# MB_RF.net
KiCad netlist of a schematic drawn in Altium Designer
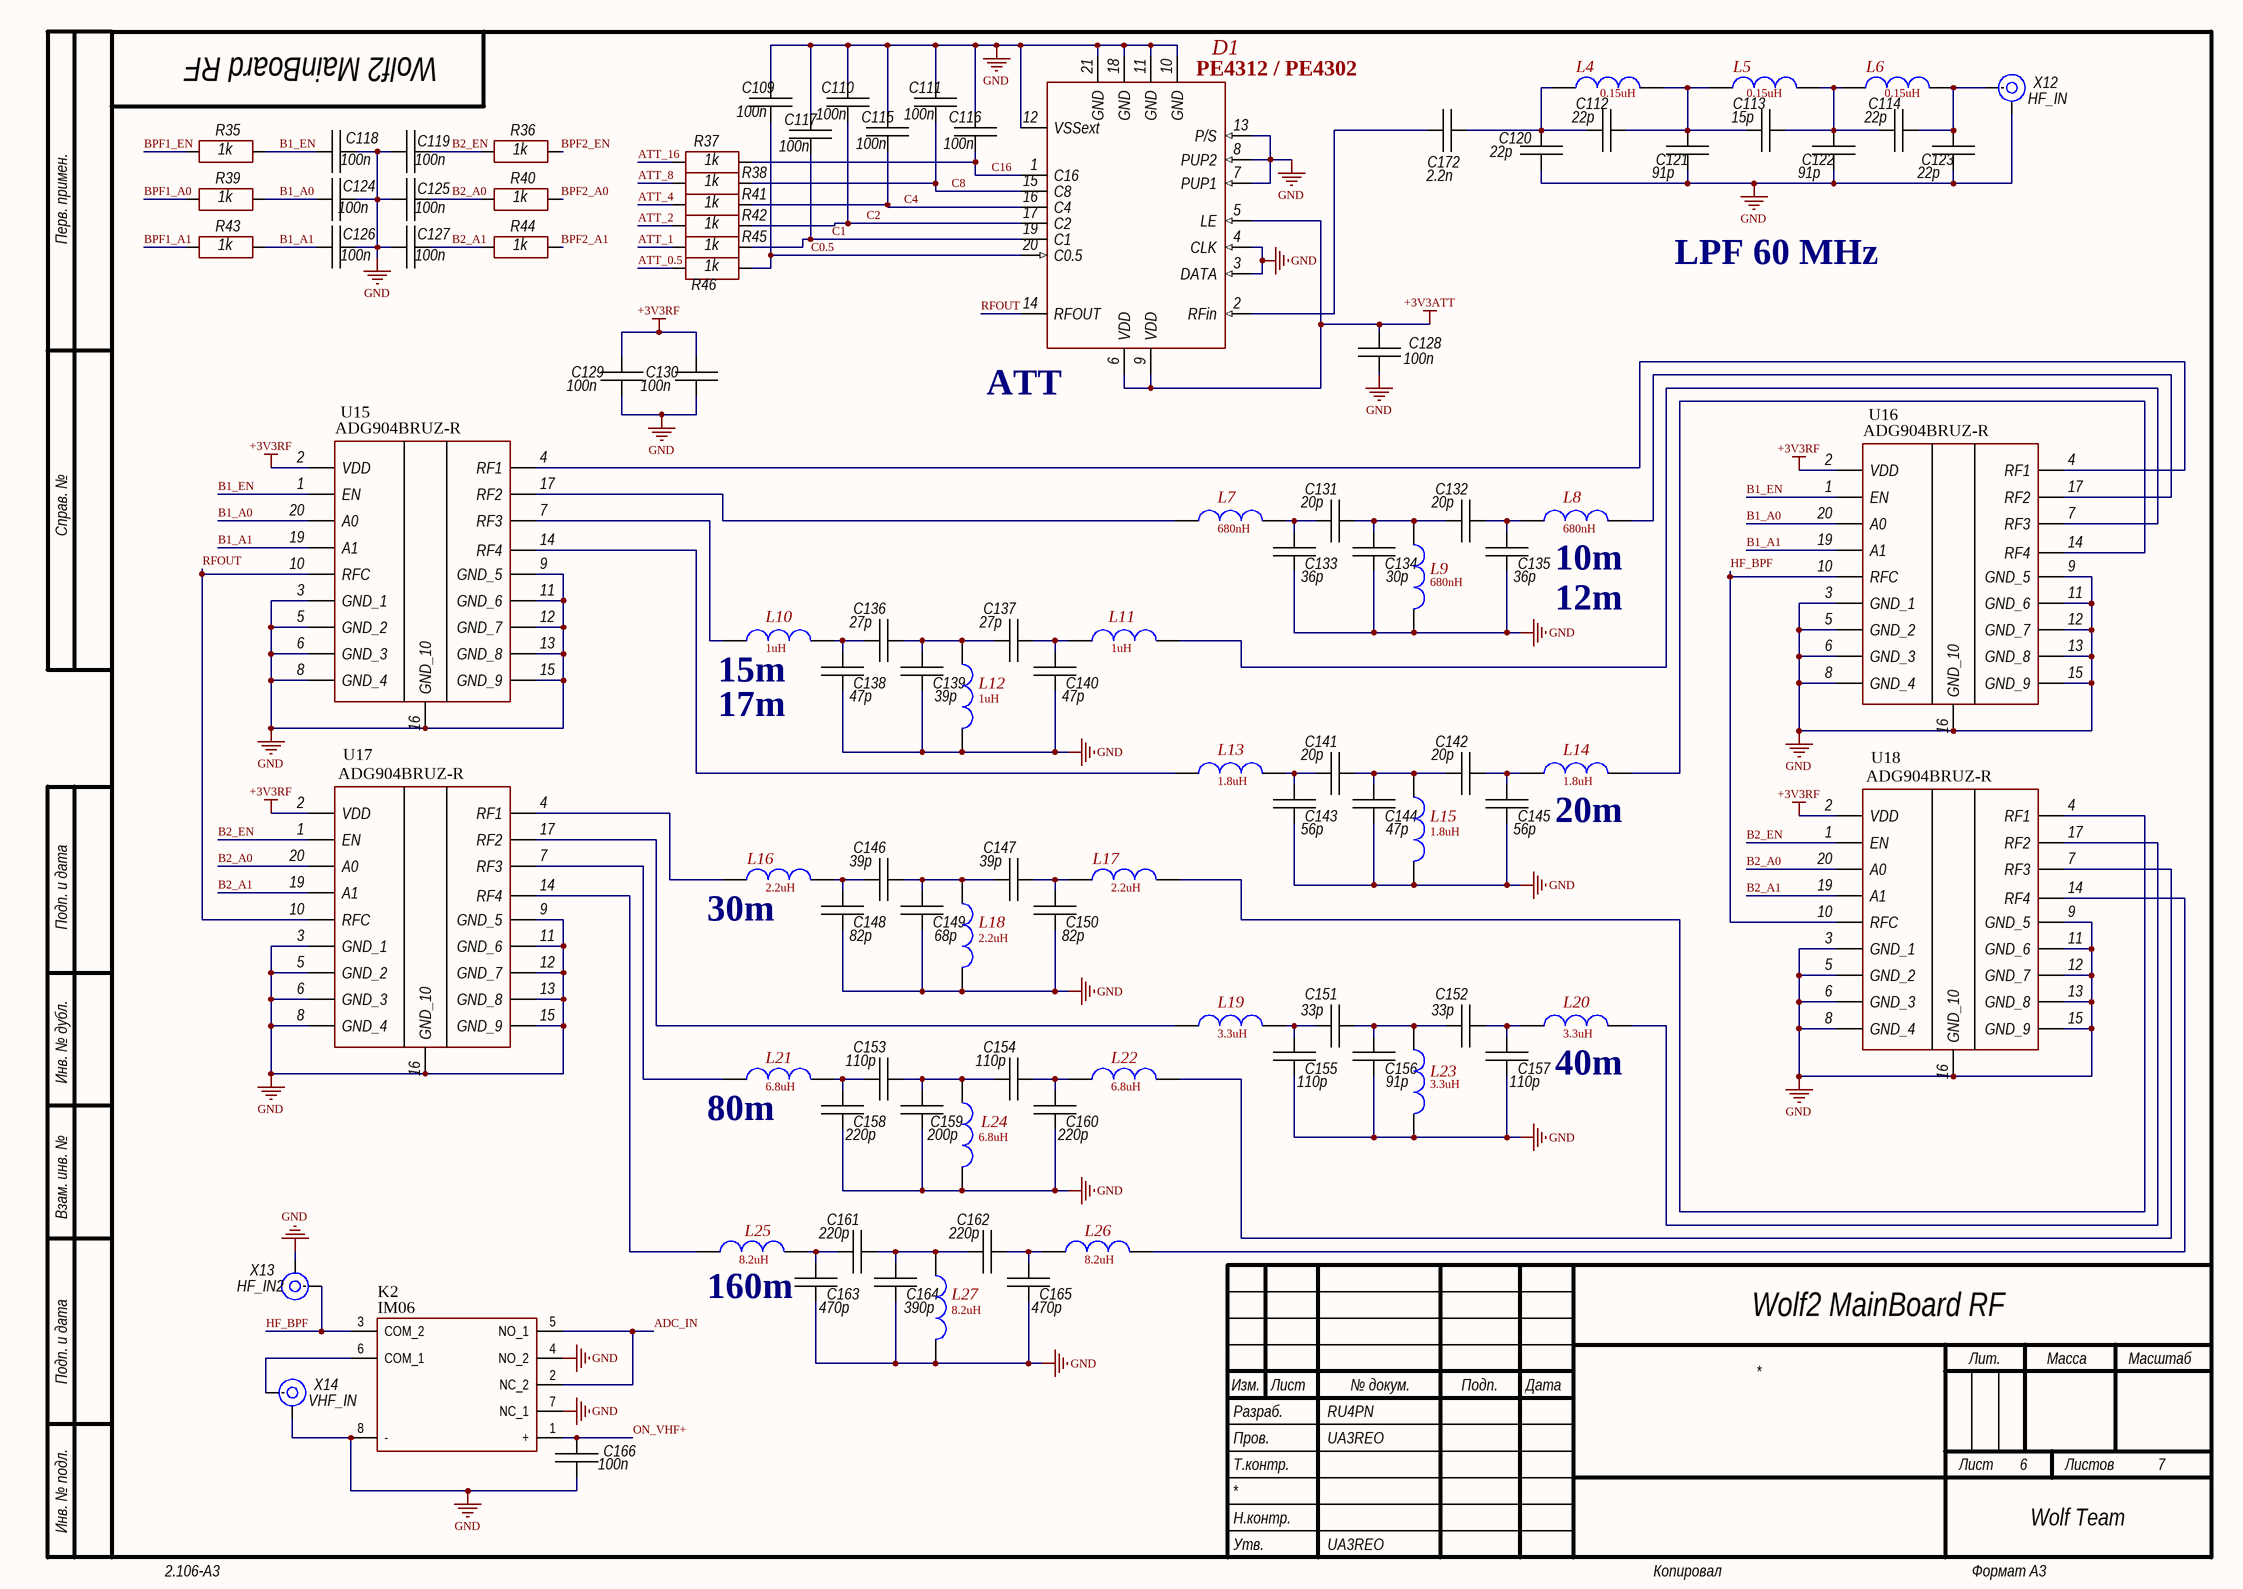
[diagram p0: MB_RF.SchDoc]

(export (version "E")
  (design (tool "Eeschema 10.0.6"))
  (components
    (comp (ref "C109")
      (value "100n")
      (footprint "standard:CH0805C")
      (libsource (lib "Discrete") (part "Capacitor"))
    )
    (comp (ref "C110")
      (value "100n")
      (footprint "standard:CH0805C")
      (libsource (lib "Discrete") (part "Capacitor"))
    )
    (comp (ref "C111")
      (value "100n")
      (footprint "standard:CH0805C")
      (libsource (lib "Discrete") (part "Capacitor"))
    )
    (comp (ref "C112")
      (value "22p")
      (footprint "standard:CH0805C")
      (libsource (lib "Discrete") (part "Capacitor"))
    )
    (comp (ref "C113")
      (value "15p")
      (footprint "standard:CH0805C")
      (libsource (lib "Discrete") (part "Capacitor"))
    )
    (comp (ref "C114")
      (value "22p")
      (footprint "standard:CH0805C")
      (libsource (lib "Discrete") (part "Capacitor"))
    )
    (comp (ref "C115")
      (value "100n")
      (footprint "standard:CH0805C")
      (libsource (lib "Discrete") (part "Capacitor"))
    )
    (comp (ref "C116")
      (value "100n")
      (footprint "standard:CH0805C")
      (libsource (lib "Discrete") (part "Capacitor"))
    )
    (comp (ref "C117")
      (value "100n")
      (footprint "standard:CH0805C")
      (libsource (lib "Discrete") (part "Capacitor"))
    )
    (comp (ref "C118")
      (value "100n")
      (footprint "standard:CH0805C")
      (libsource (lib "Discrete") (part "Capacitor"))
    )
    (comp (ref "C119")
      (value "100n")
      (footprint "standard:CH0805C")
      (libsource (lib "Discrete") (part "Capacitor"))
    )
    (comp (ref "C120")
      (value "22p")
      (footprint "standard:CH0805C")
      (libsource (lib "Discrete") (part "Capacitor"))
    )
    (comp (ref "C121")
      (value "91p")
      (footprint "standard:CH0805C")
      (libsource (lib "Discrete") (part "Capacitor"))
    )
    (comp (ref "C122")
      (value "91p")
      (footprint "standard:CH0805C")
      (libsource (lib "Discrete") (part "Capacitor"))
    )
    (comp (ref "C123")
      (value "22p")
      (footprint "standard:CH0805C")
      (libsource (lib "Discrete") (part "Capacitor"))
    )
    (comp (ref "C124")
      (value "100n")
      (footprint "standard:CH0805C")
      (libsource (lib "Discrete") (part "Capacitor"))
    )
    (comp (ref "C125")
      (value "100n")
      (footprint "standard:CH0805C")
      (libsource (lib "Discrete") (part "Capacitor"))
    )
    (comp (ref "C126")
      (value "100n")
      (footprint "standard:CH0805C")
      (libsource (lib "") (part "Capacitor_2"))
    )
    (comp (ref "C127")
      (value "100n")
      (footprint "standard:CH0805C")
      (libsource (lib "") (part "Capacitor_2"))
    )
    (comp (ref "C128")
      (value "100n")
      (footprint "standard:CH0805C")
      (libsource (lib "Discrete") (part "Capacitor"))
    )
    (comp (ref "C129")
      (value "100n")
      (footprint "standard:CH0805C")
      (libsource (lib "Discrete") (part "Capacitor"))
    )
    (comp (ref "C130")
      (value "100n")
      (footprint "standard:CH0805C")
      (libsource (lib "Discrete") (part "Capacitor"))
    )
    (comp (ref "C131") (value "20p") (footprint "standard:CH0805C") (libsource (lib "") (part "Capacitor_1")))
    (comp (ref "C132")
      (value "20p")
      (footprint "standard:CH0805C")
      (libsource (lib "Discrete") (part "Capacitor"))
    )
    (comp (ref "C133")
      (value "36p")
      (footprint "standard:CH0805C")
      (libsource (lib "Discrete") (part "Capacitor"))
    )
    (comp (ref "C134")
      (value "30p")
      (footprint "standard:CH0805C")
      (libsource (lib "Discrete") (part "Capacitor"))
    )
    (comp (ref "C135")
      (value "36p")
      (footprint "standard:CH0805C")
      (libsource (lib "Discrete") (part "Capacitor"))
    )
    (comp (ref "C136")
      (value "27p")
      (footprint "standard:CH0805C")
      (libsource (lib "Discrete") (part "Capacitor"))
    )
    (comp (ref "C137")
      (value "27p")
      (footprint "standard:CH0805C")
      (libsource (lib "Discrete") (part "Capacitor"))
    )
    (comp (ref "C138")
      (value "47p")
      (footprint "standard:CH0805C")
      (libsource (lib "Discrete") (part "Capacitor"))
    )
    (comp (ref "C139")
      (value "39p")
      (footprint "standard:CH0805C")
      (libsource (lib "Discrete") (part "Capacitor"))
    )
    (comp (ref "C140")
      (value "47p")
      (footprint "standard:CH0805C")
      (libsource (lib "Discrete") (part "Capacitor"))
    )
    (comp (ref "C141") (value "20p") (footprint "standard:CH0805C") (libsource (lib "") (part "Capacitor_1")))
    (comp (ref "C142")
      (value "20p")
      (footprint "standard:CH0805C")
      (libsource (lib "Discrete") (part "Capacitor"))
    )
    (comp (ref "C143")
      (value "56p")
      (footprint "standard:CH0805C")
      (libsource (lib "Discrete") (part "Capacitor"))
    )
    (comp (ref "C144")
      (value "47p")
      (footprint "standard:CH0805C")
      (libsource (lib "Discrete") (part "Capacitor"))
    )
    (comp (ref "C145")
      (value "56p")
      (footprint "standard:CH0805C")
      (libsource (lib "Discrete") (part "Capacitor"))
    )
    (comp (ref "C146")
      (value "39p")
      (footprint "standard:CH0805C")
      (libsource (lib "Discrete") (part "Capacitor"))
    )
    (comp (ref "C147")
      (value "39p")
      (footprint "standard:CH0805C")
      (libsource (lib "Discrete") (part "Capacitor"))
    )
    (comp (ref "C148")
      (value "82p")
      (footprint "standard:CH0805C")
      (libsource (lib "Discrete") (part "Capacitor"))
    )
    (comp (ref "C149")
      (value "68p")
      (footprint "standard:CH0805C")
      (libsource (lib "Discrete") (part "Capacitor"))
    )
    (comp (ref "C150")
      (value "82p")
      (footprint "standard:CH0805C")
      (libsource (lib "Discrete") (part "Capacitor"))
    )
    (comp (ref "C151") (value "33p") (footprint "standard:CH0805C") (libsource (lib "") (part "Capacitor_1")))
    (comp (ref "C152")
      (value "33p")
      (footprint "standard:CH0805C")
      (libsource (lib "Discrete") (part "Capacitor"))
    )
    (comp (ref "C153")
      (value "110p")
      (footprint "standard:CH0805C")
      (libsource (lib "Discrete") (part "Capacitor"))
    )
    (comp (ref "C154")
      (value "110p")
      (footprint "standard:CH0805C")
      (libsource (lib "Discrete") (part "Capacitor"))
    )
    (comp (ref "C155")
      (value "110p")
      (footprint "standard:CH0805C")
      (libsource (lib "Discrete") (part "Capacitor"))
    )
    (comp (ref "C156")
      (value "91p")
      (footprint "standard:CH0805C")
      (libsource (lib "Discrete") (part "Capacitor"))
    )
    (comp (ref "C157")
      (value "110p")
      (footprint "standard:CH0805C")
      (libsource (lib "Discrete") (part "Capacitor"))
    )
    (comp (ref "C158")
      (value "220p")
      (footprint "standard:CH0805C")
      (libsource (lib "Discrete") (part "Capacitor"))
    )
    (comp (ref "C159")
      (value "200p")
      (footprint "standard:CH0805C")
      (libsource (lib "Discrete") (part "Capacitor"))
    )
    (comp (ref "C160")
      (value "220p")
      (footprint "standard:CH0805C")
      (libsource (lib "Discrete") (part "Capacitor"))
    )
    (comp (ref "C161")
      (value "220p")
      (footprint "standard:CH0805C")
      (libsource (lib "Discrete") (part "Capacitor"))
    )
    (comp (ref "C162")
      (value "220p")
      (footprint "standard:CH0805C")
      (libsource (lib "Discrete") (part "Capacitor"))
    )
    (comp (ref "C163")
      (value "470p")
      (footprint "standard:CH0805C")
      (libsource (lib "Discrete") (part "Capacitor"))
    )
    (comp (ref "C164")
      (value "390p")
      (footprint "standard:CH0805C")
      (libsource (lib "Discrete") (part "Capacitor"))
    )
    (comp (ref "C165")
      (value "470p")
      (footprint "standard:CH0805C")
      (libsource (lib "Discrete") (part "Capacitor"))
    )
    (comp (ref "C166")
      (value "100n")
      (footprint "standard:CH0805C")
      (libsource (lib "Discrete") (part "Capacitor"))
    )
    (comp (ref "C172")
      (value "2.2n")
      (footprint "standard:CH0805C")
      (libsource (lib "Discrete") (part "Capacitor"))
    )
    (comp (ref "D1")
      (value "PE4312 / PE4302")
      (footprint "20-QFN (4x4)")
      (libsource (lib "Digital") (part "PE4312-№1"))
    )
    (comp (ref "K2") (value "IM06") (footprint "IM06") (libsource (lib "Relay") (part "IM06-V1")))
    (comp (ref "L4") (value "0.15uH") (footprint "CH0805L") (libsource (lib "Discrete") (part "Inductor-2")))
    (comp (ref "L5") (value "0.15uH") (footprint "CH0805L") (libsource (lib "Discrete") (part "Inductor-2")))
    (comp (ref "L6") (value "0.15uH") (footprint "CH0805L") (libsource (lib "Discrete") (part "Inductor-2")))
    (comp (ref "L7") (value "680nH") (footprint "CH0805L") (libsource (lib "Discrete") (part "Inductor-2")))
    (comp (ref "L8") (value "680nH") (footprint "CH0805L") (libsource (lib "Discrete") (part "Inductor-2")))
    (comp (ref "L9") (value "680nH") (footprint "CH0805L") (libsource (lib "Discrete") (part "Inductor-2")))
    (comp (ref "L10") (value "1uH") (footprint "CH0805L") (libsource (lib "Discrete") (part "Inductor-2")))
    (comp (ref "L11") (value "1uH") (footprint "CH0805L") (libsource (lib "Discrete") (part "Inductor-2")))
    (comp (ref "L12") (value "1uH") (footprint "CH0805L") (libsource (lib "Discrete") (part "Inductor-2")))
    (comp (ref "L13") (value "1.8uH") (footprint "CH0805L") (libsource (lib "Discrete") (part "Inductor-2")))
    (comp (ref "L14") (value "1.8uH") (footprint "CH0805L") (libsource (lib "Discrete") (part "Inductor-2")))
    (comp (ref "L15") (value "1.8uH") (footprint "CH0805L") (libsource (lib "Discrete") (part "Inductor-2")))
    (comp (ref "L16") (value "2.2uH") (footprint "CH0805L") (libsource (lib "Discrete") (part "Inductor-2")))
    (comp (ref "L17") (value "2.2uH") (footprint "CH0805L") (libsource (lib "Discrete") (part "Inductor-2")))
    (comp (ref "L18") (value "2.2uH") (footprint "CH0805L") (libsource (lib "Discrete") (part "Inductor-2")))
    (comp (ref "L19") (value "3.3uH") (footprint "CH0805L") (libsource (lib "Discrete") (part "Inductor-2")))
    (comp (ref "L20") (value "3.3uH") (footprint "CH0805L") (libsource (lib "Discrete") (part "Inductor-2")))
    (comp (ref "L21") (value "6.8uH") (footprint "CH0805L") (libsource (lib "Discrete") (part "Inductor-2")))
    (comp (ref "L22") (value "6.8uH") (footprint "CH0805L") (libsource (lib "Discrete") (part "Inductor-2")))
    (comp (ref "L23") (value "3.3uH") (footprint "CH0805L") (libsource (lib "Discrete") (part "Inductor-2")))
    (comp (ref "L24") (value "6.8uH") (footprint "CH0805L") (libsource (lib "Discrete") (part "Inductor-2")))
    (comp (ref "L25") (value "8.2uH") (footprint "CH0805L") (libsource (lib "Discrete") (part "Inductor-2")))
    (comp (ref "L26") (value "8.2uH") (footprint "CH0805L") (libsource (lib "Discrete") (part "Inductor-2")))
    (comp (ref "L27") (value "8.2uH") (footprint "CH0805L") (libsource (lib "Discrete") (part "Inductor-2")))
    (comp (ref "R35")
      (value "1k")
      (footprint "standard:CH0805R")
      (libsource (lib "Discrete") (part "Resistor"))
    )
    (comp (ref "R36")
      (value "1k")
      (footprint "standard:CH0805R")
      (libsource (lib "Discrete") (part "Resistor"))
    )
    (comp (ref "R37")
      (value "1k")
      (footprint "standard:CH0805R")
      (libsource (lib "Discrete") (part "Resistor"))
    )
    (comp (ref "R38")
      (value "1k")
      (footprint "standard:CH0805R")
      (libsource (lib "Discrete") (part "Resistor"))
    )
    (comp (ref "R39")
      (value "1k")
      (footprint "standard:CH0805R")
      (libsource (lib "Discrete") (part "Resistor"))
    )
    (comp (ref "R40")
      (value "1k")
      (footprint "standard:CH0805R")
      (libsource (lib "Discrete") (part "Resistor"))
    )
    (comp (ref "R41")
      (value "1k")
      (footprint "standard:CH0805R")
      (libsource (lib "Discrete") (part "Resistor"))
    )
    (comp (ref "R42")
      (value "1k")
      (footprint "standard:CH0805R")
      (libsource (lib "Discrete") (part "Resistor"))
    )
    (comp (ref "R43") (value "1k") (footprint "standard:CH0805R") (libsource (lib "") (part "Resistor_1")))
    (comp (ref "R44") (value "1k") (footprint "standard:CH0805R") (libsource (lib "") (part "Resistor_1")))
    (comp (ref "R45") (value "1k") (footprint "standard:CH0805R") (libsource (lib "") (part "Resistor_1")))
    (comp (ref "R46")
      (value "1k")
      (footprint "standard:CH0805R")
      (libsource (lib "Discrete") (part "Resistor"))
    )
    (comp (ref "U15")
      (value "ADG904BRUZ-R")
      (footprint "20-TSSOP")
      (libsource (lib "Digital") (part "ADG904BRUZ-R"))
    )
    (comp (ref "U16")
      (value "ADG904BRUZ-R")
      (footprint "20-TSSOP")
      (libsource (lib "Digital") (part "ADG904BRUZ-R"))
    )
    (comp (ref "U17")
      (value "ADG904BRUZ-R")
      (footprint "20-TSSOP")
      (libsource (lib "Digital") (part "ADG904BRUZ-R"))
    )
    (comp (ref "U18")
      (value "ADG904BRUZ-R")
      (footprint "20-TSSOP")
      (libsource (lib "Digital") (part "ADG904BRUZ-R"))
    )
    (comp (ref "X12")
      (value "HF_IN")
      (footprint "custom:CON: SMA")
      (description "RF")
      (libsource (lib "Connectors") (part "SMA"))
    )
    (comp (ref "X13")
      (value "HF_IN2")
      (footprint "custom:CON: SMA")
      (description "RF")
      (libsource (lib "Connectors") (part "SMA"))
    )
    (comp (ref "X14")
      (value "VHF_IN")
      (footprint "custom:CON: SMA")
      (description "RF")
      (libsource (lib "Connectors") (part "SMA"))
    )
  )
  (nets
    (net (code "1") (name "+3V3ATT") (class "Default")
      (node (ref "C128") (pin "1") (pinfunction "1_1") (pintype "power_in"))
      (node (ref "D1") (pin "5") (pinfunction "LE_5") (pintype "input"))
      (node (ref "D1") (pin "6") (pinfunction "VDD_6") (pintype "passive"))
      (node (ref "D1") (pin "9") (pinfunction "VDD_9") (pintype "passive"))
    )
    (net (code "2") (name "+3V3RF") (class "Default")
      (node (ref "C129") (pin "1") (pinfunction "1_1") (pintype "power_in"))
      (node (ref "C130") (pin "1") (pinfunction "1_1") (pintype "power_in"))
      (node (ref "U15") (pin "2") (pinfunction "VDD_2") (pintype "passive"))
      (node (ref "U16") (pin "2") (pinfunction "VDD_2") (pintype "passive"))
      (node (ref "U17") (pin "2") (pinfunction "VDD_2") (pintype "passive"))
      (node (ref "U18") (pin "2") (pinfunction "VDD_2") (pintype "passive"))
    )
    (net (code "3") (name "/ADC_IN") (class "Default")
      (node (ref "K2") (pin "2") (pinfunction "NC_2_2") (pintype "passive"))
      (node (ref "K2") (pin "5") (pinfunction "NO_1_5") (pintype "passive"))
    )
    (net (code "4") (name "/ATT_0.5") (class "Default")
      (node (ref "R46") (pin "2") (pinfunction "2_2") (pintype "passive"))
    )
    (net (code "5") (name "/ATT_1") (class "Default")
      (node (ref "R45") (pin "2") (pinfunction "2_2") (pintype "passive"))
    )
    (net (code "6") (name "/ATT_2") (class "Default")
      (node (ref "R42") (pin "2") (pinfunction "2_2") (pintype "passive"))
    )
    (net (code "7") (name "/ATT_4") (class "Default")
      (node (ref "R41") (pin "2") (pinfunction "2_2") (pintype "passive"))
    )
    (net (code "8") (name "/ATT_8") (class "Default")
      (node (ref "R38") (pin "2") (pinfunction "2_2") (pintype "passive"))
    )
    (net (code "9") (name "/ATT_16") (class "Default")
      (node (ref "R37") (pin "2") (pinfunction "2_2") (pintype "passive"))
    )
    (net (code "10") (name "/B1_A0") (class "Default")
      (node (ref "C124") (pin "1") (pinfunction "1_1") (pintype "power_in"))
      (node (ref "R39") (pin "1") (pinfunction "1_1") (pintype "passive"))
      (node (ref "U15") (pin "20") (pinfunction "A0_20") (pintype "passive"))
      (node (ref "U16") (pin "20") (pinfunction "A0_20") (pintype "passive"))
    )
    (net (code "11") (name "/B1_A1") (class "Default")
      (node (ref "C126") (pin "1") (pinfunction "1_1") (pintype "power_in"))
      (node (ref "R43") (pin "1") (pinfunction "1_1") (pintype "passive"))
      (node (ref "U15") (pin "19") (pinfunction "A1_19") (pintype "passive"))
      (node (ref "U16") (pin "19") (pinfunction "A1_19") (pintype "passive"))
    )
    (net (code "12") (name "/B1_EN") (class "Default")
      (node (ref "C118") (pin "1") (pinfunction "1_1") (pintype "power_in"))
      (node (ref "R35") (pin "1") (pinfunction "1_1") (pintype "passive"))
      (node (ref "U15") (pin "1") (pinfunction "EN_1") (pintype "passive"))
      (node (ref "U16") (pin "1") (pinfunction "EN_1") (pintype "passive"))
    )
    (net (code "13") (name "/B2_A0") (class "Default")
      (node (ref "C125") (pin "2") (pinfunction "2_2") (pintype "power_in"))
      (node (ref "R40") (pin "2") (pinfunction "2_2") (pintype "passive"))
      (node (ref "U17") (pin "20") (pinfunction "A0_20") (pintype "passive"))
      (node (ref "U18") (pin "20") (pinfunction "A0_20") (pintype "passive"))
    )
    (net (code "14") (name "/B2_A1") (class "Default")
      (node (ref "C127") (pin "2") (pinfunction "2_2") (pintype "power_in"))
      (node (ref "R44") (pin "2") (pinfunction "2_2") (pintype "passive"))
      (node (ref "U17") (pin "19") (pinfunction "A1_19") (pintype "passive"))
      (node (ref "U18") (pin "19") (pinfunction "A1_19") (pintype "passive"))
    )
    (net (code "15") (name "/B2_EN") (class "Default")
      (node (ref "C119") (pin "2") (pinfunction "2_2") (pintype "power_in"))
      (node (ref "R36") (pin "2") (pinfunction "2_2") (pintype "passive"))
      (node (ref "U17") (pin "1") (pinfunction "EN_1") (pintype "passive"))
      (node (ref "U18") (pin "1") (pinfunction "EN_1") (pintype "passive"))
    )
    (net (code "16") (name "/BPF1_A0") (class "Default")
      (node (ref "R39") (pin "2") (pinfunction "2_2") (pintype "passive"))
    )
    (net (code "17") (name "/BPF1_A1") (class "Default")
      (node (ref "R43") (pin "2") (pinfunction "2_2") (pintype "passive"))
    )
    (net (code "18") (name "/BPF1_EN") (class "Default")
      (node (ref "R35") (pin "2") (pinfunction "2_2") (pintype "passive"))
    )
    (net (code "19") (name "/BPF2_A0") (class "Default")
      (node (ref "R40") (pin "1") (pinfunction "1_1") (pintype "passive"))
    )
    (net (code "20") (name "/BPF2_A1") (class "Default")
      (node (ref "R44") (pin "1") (pinfunction "1_1") (pintype "passive"))
    )
    (net (code "21") (name "/BPF2_EN") (class "Default")
      (node (ref "R36") (pin "1") (pinfunction "1_1") (pintype "passive"))
    )
    (net (code "22") (name "/C0.5") (class "Default")
      (node (ref "C109") (pin "2") (pinfunction "2_2") (pintype "power_in"))
      (node (ref "D1") (pin "20") (pinfunction "С0.5_20") (pintype "input"))
      (node (ref "R46") (pin "1") (pinfunction "1_1") (pintype "passive"))
    )
    (net (code "23") (name "/C1") (class "Default")
      (node (ref "C117") (pin "2") (pinfunction "2_2") (pintype "power_in"))
      (node (ref "D1") (pin "19") (pinfunction "C1_19") (pintype "passive"))
      (node (ref "R45") (pin "1") (pinfunction "1_1") (pintype "passive"))
    )
    (net (code "24") (name "/C2") (class "Default")
      (node (ref "C110") (pin "2") (pinfunction "2_2") (pintype "power_in"))
      (node (ref "D1") (pin "17") (pinfunction "C2_17") (pintype "passive"))
      (node (ref "R42") (pin "1") (pinfunction "1_1") (pintype "passive"))
    )
    (net (code "25") (name "/C4") (class "Default")
      (node (ref "C115") (pin "2") (pinfunction "2_2") (pintype "power_in"))
      (node (ref "D1") (pin "16") (pinfunction "C4_16") (pintype "passive"))
      (node (ref "R41") (pin "1") (pinfunction "1_1") (pintype "passive"))
    )
    (net (code "26") (name "/C8") (class "Default")
      (node (ref "C111") (pin "2") (pinfunction "2_2") (pintype "power_in"))
      (node (ref "D1") (pin "15") (pinfunction "C8_15") (pintype "passive"))
      (node (ref "R38") (pin "1") (pinfunction "1_1") (pintype "passive"))
    )
    (net (code "27") (name "/C16") (class "Default")
      (node (ref "C116") (pin "2") (pinfunction "2_2") (pintype "power_in"))
      (node (ref "D1") (pin "1") (pinfunction "C16_1") (pintype "passive"))
      (node (ref "R37") (pin "1") (pinfunction "1_1") (pintype "passive"))
    )
    (net (code "28") (name "/HF_BPF") (class "Default")
      (node (ref "K2") (pin "3") (pinfunction "COM_2_3") (pintype "passive"))
      (node (ref "U16") (pin "10") (pinfunction "RFC_10") (pintype "passive"))
      (node (ref "U18") (pin "10") (pinfunction "RFC_10") (pintype "passive"))
      (node (ref "X13") (pin "1") (pinfunction "IN_1") (pintype "passive"))
    )
    (net (code "29") (name "/ON_VHF+") (class "Default")
      (node (ref "C166") (pin "2") (pinfunction "2_2") (pintype "power_in"))
      (node (ref "K2") (pin "1") (pinfunction "+_1") (pintype "passive"))
    )
    (net (code "30") (name "/RFOUT") (class "Default")
      (node (ref "D1") (pin "14") (pinfunction "RFOUT_14") (pintype "passive"))
      (node (ref "U15") (pin "10") (pinfunction "RFC_10") (pintype "passive"))
      (node (ref "U17") (pin "10") (pinfunction "RFC_10") (pintype "passive"))
    )
    (net (code "31") (name "GND") (class "Default")
      (node (ref "C109") (pin "1") (pinfunction "1_1") (pintype "power_in"))
      (node (ref "C110") (pin "1") (pinfunction "1_1") (pintype "power_in"))
      (node (ref "C111") (pin "1") (pinfunction "1_1") (pintype "power_in"))
      (node (ref "C115") (pin "1") (pinfunction "1_1") (pintype "power_in"))
      (node (ref "C116") (pin "1") (pinfunction "1_1") (pintype "power_in"))
      (node (ref "C117") (pin "1") (pinfunction "1_1") (pintype "power_in"))
      (node (ref "C118") (pin "2") (pinfunction "2_2") (pintype "power_in"))
      (node (ref "C119") (pin "1") (pinfunction "1_1") (pintype "power_in"))
      (node (ref "C120") (pin "2") (pinfunction "2_2") (pintype "power_in"))
      (node (ref "C121") (pin "2") (pinfunction "2_2") (pintype "power_in"))
      (node (ref "C122") (pin "2") (pinfunction "2_2") (pintype "power_in"))
      (node (ref "C123") (pin "2") (pinfunction "2_2") (pintype "power_in"))
      (node (ref "C124") (pin "2") (pinfunction "2_2") (pintype "power_in"))
      (node (ref "C125") (pin "1") (pinfunction "1_1") (pintype "power_in"))
      (node (ref "C126") (pin "2") (pinfunction "2_2") (pintype "power_in"))
      (node (ref "C127") (pin "1") (pinfunction "1_1") (pintype "power_in"))
      (node (ref "C128") (pin "2") (pinfunction "2_2") (pintype "power_in"))
      (node (ref "C129") (pin "2") (pinfunction "2_2") (pintype "power_in"))
      (node (ref "C130") (pin "2") (pinfunction "2_2") (pintype "power_in"))
      (node (ref "C133") (pin "1") (pinfunction "1_1") (pintype "power_in"))
      (node (ref "C134") (pin "1") (pinfunction "1_1") (pintype "power_in"))
      (node (ref "C135") (pin "1") (pinfunction "1_1") (pintype "power_in"))
      (node (ref "C138") (pin "1") (pinfunction "1_1") (pintype "power_in"))
      (node (ref "C139") (pin "1") (pinfunction "1_1") (pintype "power_in"))
      (node (ref "C140") (pin "1") (pinfunction "1_1") (pintype "power_in"))
      (node (ref "C143") (pin "1") (pinfunction "1_1") (pintype "power_in"))
      (node (ref "C144") (pin "1") (pinfunction "1_1") (pintype "power_in"))
      (node (ref "C145") (pin "1") (pinfunction "1_1") (pintype "power_in"))
      (node (ref "C148") (pin "1") (pinfunction "1_1") (pintype "power_in"))
      (node (ref "C149") (pin "1") (pinfunction "1_1") (pintype "power_in"))
      (node (ref "C150") (pin "1") (pinfunction "1_1") (pintype "power_in"))
      (node (ref "C155") (pin "1") (pinfunction "1_1") (pintype "power_in"))
      (node (ref "C156") (pin "1") (pinfunction "1_1") (pintype "power_in"))
      (node (ref "C157") (pin "1") (pinfunction "1_1") (pintype "power_in"))
      (node (ref "C158") (pin "1") (pinfunction "1_1") (pintype "power_in"))
      (node (ref "C159") (pin "1") (pinfunction "1_1") (pintype "power_in"))
      (node (ref "C160") (pin "1") (pinfunction "1_1") (pintype "power_in"))
      (node (ref "C163") (pin "1") (pinfunction "1_1") (pintype "power_in"))
      (node (ref "C164") (pin "1") (pinfunction "1_1") (pintype "power_in"))
      (node (ref "C165") (pin "1") (pinfunction "1_1") (pintype "power_in"))
      (node (ref "C166") (pin "1") (pinfunction "1_1") (pintype "power_in"))
      (node (ref "D1") (pin "10") (pinfunction "GND_10") (pintype "passive"))
      (node (ref "D1") (pin "11") (pinfunction "GND_11") (pintype "passive"))
      (node (ref "D1") (pin "12") (pinfunction "VSSext_12") (pintype "passive"))
      (node (ref "D1") (pin "13") (pinfunction "P/S_13") (pintype "input"))
      (node (ref "D1") (pin "18") (pinfunction "GND_18") (pintype "passive"))
      (node (ref "D1") (pin "21") (pinfunction "GND_21") (pintype "passive"))
      (node (ref "D1") (pin "3") (pinfunction "DATA_3") (pintype "input"))
      (node (ref "D1") (pin "4") (pinfunction "CLK_4") (pintype "input"))
      (node (ref "D1") (pin "7") (pinfunction "PUP1_7") (pintype "input"))
      (node (ref "D1") (pin "8") (pinfunction "PUP2_8") (pintype "input"))
      (node (ref "K2") (pin "4") (pinfunction "NO_2_4") (pintype "passive"))
      (node (ref "K2") (pin "7") (pinfunction "NC_1_7") (pintype "passive"))
      (node (ref "K2") (pin "8") (pinfunction "-_8") (pintype "passive"))
      (node (ref "L12") (pin "1") (pinfunction "1_1") (pintype "passive"))
      (node (ref "L15") (pin "1") (pinfunction "1_1") (pintype "passive"))
      (node (ref "L18") (pin "1") (pinfunction "1_1") (pintype "passive"))
      (node (ref "L23") (pin "1") (pinfunction "1_1") (pintype "passive"))
      (node (ref "L24") (pin "1") (pinfunction "1_1") (pintype "passive"))
      (node (ref "L27") (pin "1") (pinfunction "1_1") (pintype "passive"))
      (node (ref "L9") (pin "1") (pinfunction "1_1") (pintype "passive"))
      (node (ref "U15") (pin "11") (pinfunction "GND_6_11") (pintype "passive"))
      (node (ref "U15") (pin "12") (pinfunction "GND_7_12") (pintype "passive"))
      (node (ref "U15") (pin "13") (pinfunction "GND_8_13") (pintype "passive"))
      (node (ref "U15") (pin "15") (pinfunction "GND_9_15") (pintype "passive"))
      (node (ref "U15") (pin "16") (pinfunction "GND_10_16") (pintype "power_in"))
      (node (ref "U15") (pin "3") (pinfunction "GND_1_3") (pintype "passive"))
      (node (ref "U15") (pin "5") (pinfunction "GND_2_5") (pintype "passive"))
      (node (ref "U15") (pin "6") (pinfunction "GND_3_6") (pintype "passive"))
      (node (ref "U15") (pin "8") (pinfunction "GND_4_8") (pintype "passive"))
      (node (ref "U15") (pin "9") (pinfunction "GND_5_9") (pintype "passive"))
      (node (ref "U16") (pin "11") (pinfunction "GND_6_11") (pintype "passive"))
      (node (ref "U16") (pin "12") (pinfunction "GND_7_12") (pintype "passive"))
      (node (ref "U16") (pin "13") (pinfunction "GND_8_13") (pintype "passive"))
      (node (ref "U16") (pin "15") (pinfunction "GND_9_15") (pintype "passive"))
      (node (ref "U16") (pin "16") (pinfunction "GND_10_16") (pintype "power_in"))
      (node (ref "U16") (pin "3") (pinfunction "GND_1_3") (pintype "passive"))
      (node (ref "U16") (pin "5") (pinfunction "GND_2_5") (pintype "passive"))
      (node (ref "U16") (pin "6") (pinfunction "GND_3_6") (pintype "passive"))
      (node (ref "U16") (pin "8") (pinfunction "GND_4_8") (pintype "passive"))
      (node (ref "U16") (pin "9") (pinfunction "GND_5_9") (pintype "passive"))
      (node (ref "U17") (pin "11") (pinfunction "GND_6_11") (pintype "passive"))
      (node (ref "U17") (pin "12") (pinfunction "GND_7_12") (pintype "passive"))
      (node (ref "U17") (pin "13") (pinfunction "GND_8_13") (pintype "passive"))
      (node (ref "U17") (pin "15") (pinfunction "GND_9_15") (pintype "passive"))
      (node (ref "U17") (pin "16") (pinfunction "GND_10_16") (pintype "power_in"))
      (node (ref "U17") (pin "3") (pinfunction "GND_1_3") (pintype "passive"))
      (node (ref "U17") (pin "5") (pinfunction "GND_2_5") (pintype "passive"))
      (node (ref "U17") (pin "6") (pinfunction "GND_3_6") (pintype "passive"))
      (node (ref "U17") (pin "8") (pinfunction "GND_4_8") (pintype "passive"))
      (node (ref "U17") (pin "9") (pinfunction "GND_5_9") (pintype "passive"))
      (node (ref "U18") (pin "11") (pinfunction "GND_6_11") (pintype "passive"))
      (node (ref "U18") (pin "12") (pinfunction "GND_7_12") (pintype "passive"))
      (node (ref "U18") (pin "13") (pinfunction "GND_8_13") (pintype "passive"))
      (node (ref "U18") (pin "15") (pinfunction "GND_9_15") (pintype "passive"))
      (node (ref "U18") (pin "16") (pinfunction "GND_10_16") (pintype "power_in"))
      (node (ref "U18") (pin "3") (pinfunction "GND_1_3") (pintype "passive"))
      (node (ref "U18") (pin "5") (pinfunction "GND_2_5") (pintype "passive"))
      (node (ref "U18") (pin "6") (pinfunction "GND_3_6") (pintype "passive"))
      (node (ref "U18") (pin "8") (pinfunction "GND_4_8") (pintype "passive"))
      (node (ref "U18") (pin "9") (pinfunction "GND_5_9") (pintype "passive"))
      (node (ref "X12") (pin "2") (pinfunction "IN_2") (pintype "passive"))
      (node (ref "X13") (pin "2") (pinfunction "IN_2") (pintype "passive"))
      (node (ref "X14") (pin "2") (pinfunction "IN_2") (pintype "passive"))
    )
    (net (code "32") (name "Net-(C112-Pad1)") (class "Default")
      (node (ref "C112") (pin "1") (pinfunction "1_1") (pintype "power_in"))
      (node (ref "C120") (pin "1") (pinfunction "1_1") (pintype "power_in"))
      (node (ref "C172") (pin "2") (pinfunction "2_2") (pintype "power_in"))
      (node (ref "L4") (pin "2") (pinfunction "2_2") (pintype "passive"))
    )
    (net (code "33") (name "Net-(C112-Pad2)") (class "Default")
      (node (ref "C112") (pin "2") (pinfunction "2_2") (pintype "power_in"))
      (node (ref "C113") (pin "1") (pinfunction "1_1") (pintype "power_in"))
      (node (ref "C121") (pin "1") (pinfunction "1_1") (pintype "power_in"))
      (node (ref "L4") (pin "1") (pinfunction "1_1") (pintype "passive"))
      (node (ref "L5") (pin "2") (pinfunction "2_2") (pintype "passive"))
    )
    (net (code "34") (name "Net-(C113-Pad2)") (class "Default")
      (node (ref "C113") (pin "2") (pinfunction "2_2") (pintype "power_in"))
      (node (ref "C114") (pin "1") (pinfunction "1_1") (pintype "power_in"))
      (node (ref "C122") (pin "1") (pinfunction "1_1") (pintype "power_in"))
      (node (ref "L5") (pin "1") (pinfunction "1_1") (pintype "passive"))
      (node (ref "L6") (pin "2") (pinfunction "2_2") (pintype "passive"))
    )
    (net (code "35") (name "Net-(C114-Pad2)") (class "Default")
      (node (ref "C114") (pin "2") (pinfunction "2_2") (pintype "power_in"))
      (node (ref "C123") (pin "1") (pinfunction "1_1") (pintype "power_in"))
      (node (ref "L6") (pin "1") (pinfunction "1_1") (pintype "passive"))
      (node (ref "X12") (pin "1") (pinfunction "IN_1") (pintype "passive"))
    )
    (net (code "36") (name "Net-(C131-Pad1)") (class "Default")
      (node (ref "C131") (pin "1") (pinfunction "1_1") (pintype "power_in"))
      (node (ref "C132") (pin "2") (pinfunction "2_2") (pintype "power_in"))
      (node (ref "C134") (pin "2") (pinfunction "2_2") (pintype "power_in"))
      (node (ref "L9") (pin "2") (pinfunction "2_2") (pintype "passive"))
    )
    (net (code "37") (name "Net-(C131-Pad2)") (class "Default")
      (node (ref "C131") (pin "2") (pinfunction "2_2") (pintype "power_in"))
      (node (ref "C133") (pin "2") (pinfunction "2_2") (pintype "power_in"))
      (node (ref "L7") (pin "1") (pinfunction "1_1") (pintype "passive"))
    )
    (net (code "38") (name "Net-(C132-Pad1)") (class "Default")
      (node (ref "C132") (pin "1") (pinfunction "1_1") (pintype "power_in"))
      (node (ref "C135") (pin "2") (pinfunction "2_2") (pintype "power_in"))
      (node (ref "L8") (pin "2") (pinfunction "2_2") (pintype "passive"))
    )
    (net (code "39") (name "Net-(C136-Pad1)") (class "Default")
      (node (ref "C136") (pin "1") (pinfunction "1_1") (pintype "power_in"))
      (node (ref "C137") (pin "2") (pinfunction "2_2") (pintype "power_in"))
      (node (ref "C139") (pin "2") (pinfunction "2_2") (pintype "power_in"))
      (node (ref "L12") (pin "2") (pinfunction "2_2") (pintype "passive"))
    )
    (net (code "40") (name "Net-(C136-Pad2)") (class "Default")
      (node (ref "C136") (pin "2") (pinfunction "2_2") (pintype "power_in"))
      (node (ref "C138") (pin "2") (pinfunction "2_2") (pintype "power_in"))
      (node (ref "L10") (pin "1") (pinfunction "1_1") (pintype "passive"))
    )
    (net (code "41") (name "Net-(C137-Pad1)") (class "Default")
      (node (ref "C137") (pin "1") (pinfunction "1_1") (pintype "power_in"))
      (node (ref "C140") (pin "2") (pinfunction "2_2") (pintype "power_in"))
      (node (ref "L11") (pin "2") (pinfunction "2_2") (pintype "passive"))
    )
    (net (code "42") (name "Net-(C141-Pad1)") (class "Default")
      (node (ref "C141") (pin "1") (pinfunction "1_1") (pintype "power_in"))
      (node (ref "C142") (pin "2") (pinfunction "2_2") (pintype "power_in"))
      (node (ref "C144") (pin "2") (pinfunction "2_2") (pintype "power_in"))
      (node (ref "L15") (pin "2") (pinfunction "2_2") (pintype "passive"))
    )
    (net (code "43") (name "Net-(C141-Pad2)") (class "Default")
      (node (ref "C141") (pin "2") (pinfunction "2_2") (pintype "power_in"))
      (node (ref "C143") (pin "2") (pinfunction "2_2") (pintype "power_in"))
      (node (ref "L13") (pin "1") (pinfunction "1_1") (pintype "passive"))
    )
    (net (code "44") (name "Net-(C142-Pad1)") (class "Default")
      (node (ref "C142") (pin "1") (pinfunction "1_1") (pintype "power_in"))
      (node (ref "C145") (pin "2") (pinfunction "2_2") (pintype "power_in"))
      (node (ref "L14") (pin "2") (pinfunction "2_2") (pintype "passive"))
    )
    (net (code "45") (name "Net-(C146-Pad1)") (class "Default")
      (node (ref "C146") (pin "1") (pinfunction "1_1") (pintype "power_in"))
      (node (ref "C147") (pin "2") (pinfunction "2_2") (pintype "power_in"))
      (node (ref "C149") (pin "2") (pinfunction "2_2") (pintype "power_in"))
      (node (ref "L18") (pin "2") (pinfunction "2_2") (pintype "passive"))
    )
    (net (code "46") (name "Net-(C146-Pad2)") (class "Default")
      (node (ref "C146") (pin "2") (pinfunction "2_2") (pintype "power_in"))
      (node (ref "C148") (pin "2") (pinfunction "2_2") (pintype "power_in"))
      (node (ref "L16") (pin "1") (pinfunction "1_1") (pintype "passive"))
    )
    (net (code "47") (name "Net-(C147-Pad1)") (class "Default")
      (node (ref "C147") (pin "1") (pinfunction "1_1") (pintype "power_in"))
      (node (ref "C150") (pin "2") (pinfunction "2_2") (pintype "power_in"))
      (node (ref "L17") (pin "2") (pinfunction "2_2") (pintype "passive"))
    )
    (net (code "48") (name "Net-(C151-Pad1)") (class "Default")
      (node (ref "C151") (pin "1") (pinfunction "1_1") (pintype "power_in"))
      (node (ref "C152") (pin "2") (pinfunction "2_2") (pintype "power_in"))
      (node (ref "C156") (pin "2") (pinfunction "2_2") (pintype "power_in"))
      (node (ref "L23") (pin "2") (pinfunction "2_2") (pintype "passive"))
    )
    (net (code "49") (name "Net-(C151-Pad2)") (class "Default")
      (node (ref "C151") (pin "2") (pinfunction "2_2") (pintype "power_in"))
      (node (ref "C155") (pin "2") (pinfunction "2_2") (pintype "power_in"))
      (node (ref "L19") (pin "1") (pinfunction "1_1") (pintype "passive"))
    )
    (net (code "50") (name "Net-(C152-Pad1)") (class "Default")
      (node (ref "C152") (pin "1") (pinfunction "1_1") (pintype "power_in"))
      (node (ref "C157") (pin "2") (pinfunction "2_2") (pintype "power_in"))
      (node (ref "L20") (pin "2") (pinfunction "2_2") (pintype "passive"))
    )
    (net (code "51") (name "Net-(C153-Pad1)") (class "Default")
      (node (ref "C153") (pin "1") (pinfunction "1_1") (pintype "power_in"))
      (node (ref "C154") (pin "2") (pinfunction "2_2") (pintype "power_in"))
      (node (ref "C159") (pin "2") (pinfunction "2_2") (pintype "power_in"))
      (node (ref "L24") (pin "2") (pinfunction "2_2") (pintype "passive"))
    )
    (net (code "52") (name "Net-(C153-Pad2)") (class "Default")
      (node (ref "C153") (pin "2") (pinfunction "2_2") (pintype "power_in"))
      (node (ref "C158") (pin "2") (pinfunction "2_2") (pintype "power_in"))
      (node (ref "L21") (pin "1") (pinfunction "1_1") (pintype "passive"))
    )
    (net (code "53") (name "Net-(C154-Pad1)") (class "Default")
      (node (ref "C154") (pin "1") (pinfunction "1_1") (pintype "power_in"))
      (node (ref "C160") (pin "2") (pinfunction "2_2") (pintype "power_in"))
      (node (ref "L22") (pin "2") (pinfunction "2_2") (pintype "passive"))
    )
    (net (code "54") (name "Net-(C161-Pad1)") (class "Default")
      (node (ref "C161") (pin "1") (pinfunction "1_1") (pintype "power_in"))
      (node (ref "C162") (pin "2") (pinfunction "2_2") (pintype "power_in"))
      (node (ref "C164") (pin "2") (pinfunction "2_2") (pintype "power_in"))
      (node (ref "L27") (pin "2") (pinfunction "2_2") (pintype "passive"))
    )
    (net (code "55") (name "Net-(C161-Pad2)") (class "Default")
      (node (ref "C161") (pin "2") (pinfunction "2_2") (pintype "power_in"))
      (node (ref "C163") (pin "2") (pinfunction "2_2") (pintype "power_in"))
      (node (ref "L25") (pin "1") (pinfunction "1_1") (pintype "passive"))
    )
    (net (code "56") (name "Net-(C162-Pad1)") (class "Default")
      (node (ref "C162") (pin "1") (pinfunction "1_1") (pintype "power_in"))
      (node (ref "C165") (pin "2") (pinfunction "2_2") (pintype "power_in"))
      (node (ref "L26") (pin "2") (pinfunction "2_2") (pintype "passive"))
    )
    (net (code "57") (name "Net-(D1-RFin)") (class "Default")
      (node (ref "C172") (pin "1") (pinfunction "1_1") (pintype "power_in"))
      (node (ref "D1") (pin "2") (pinfunction "RFin_2") (pintype "input"))
    )
    (net (code "58") (name "Net-(K2-COM_1)") (class "Default")
      (node (ref "K2") (pin "6") (pinfunction "COM_1_6") (pintype "passive"))
      (node (ref "X14") (pin "1") (pinfunction "IN_1") (pintype "passive"))
    )
    (net (code "59") (name "Net-(U15-RF1)") (class "Default")
      (node (ref "U15") (pin "4") (pinfunction "RF1_4") (pintype "passive"))
      (node (ref "U16") (pin "4") (pinfunction "RF1_4") (pintype "passive"))
    )
    (net (code "60") (name "Net-(U15-RF2)") (class "Default")
      (node (ref "L7") (pin "2") (pinfunction "2_2") (pintype "passive"))
      (node (ref "U15") (pin "17") (pinfunction "RF2_17") (pintype "passive"))
    )
    (net (code "61") (name "Net-(U15-RF3)") (class "Default")
      (node (ref "L10") (pin "2") (pinfunction "2_2") (pintype "passive"))
      (node (ref "U15") (pin "7") (pinfunction "RF3_7") (pintype "passive"))
    )
    (net (code "62") (name "Net-(U15-RF4)") (class "Default")
      (node (ref "L13") (pin "2") (pinfunction "2_2") (pintype "passive"))
      (node (ref "U15") (pin "14") (pinfunction "RF4_14") (pintype "passive"))
    )
    (net (code "63") (name "Net-(U16-RF2)") (class "Default")
      (node (ref "L8") (pin "1") (pinfunction "1_1") (pintype "passive"))
      (node (ref "U16") (pin "17") (pinfunction "RF2_17") (pintype "passive"))
    )
    (net (code "64") (name "Net-(U16-RF3)") (class "Default")
      (node (ref "L11") (pin "1") (pinfunction "1_1") (pintype "passive"))
      (node (ref "U16") (pin "7") (pinfunction "RF3_7") (pintype "passive"))
    )
    (net (code "65") (name "Net-(U16-RF4)") (class "Default")
      (node (ref "L14") (pin "1") (pinfunction "1_1") (pintype "passive"))
      (node (ref "U16") (pin "14") (pinfunction "RF4_14") (pintype "passive"))
    )
    (net (code "66") (name "Net-(U17-RF1)") (class "Default")
      (node (ref "L16") (pin "2") (pinfunction "2_2") (pintype "passive"))
      (node (ref "U17") (pin "4") (pinfunction "RF1_4") (pintype "passive"))
    )
    (net (code "67") (name "Net-(U17-RF2)") (class "Default")
      (node (ref "L19") (pin "2") (pinfunction "2_2") (pintype "passive"))
      (node (ref "U17") (pin "17") (pinfunction "RF2_17") (pintype "passive"))
    )
    (net (code "68") (name "Net-(U17-RF3)") (class "Default")
      (node (ref "L21") (pin "2") (pinfunction "2_2") (pintype "passive"))
      (node (ref "U17") (pin "7") (pinfunction "RF3_7") (pintype "passive"))
    )
    (net (code "69") (name "Net-(U17-RF4)") (class "Default")
      (node (ref "L25") (pin "2") (pinfunction "2_2") (pintype "passive"))
      (node (ref "U17") (pin "14") (pinfunction "RF4_14") (pintype "passive"))
    )
    (net (code "70") (name "Net-(U18-RF1)") (class "Default")
      (node (ref "L17") (pin "1") (pinfunction "1_1") (pintype "passive"))
      (node (ref "U18") (pin "4") (pinfunction "RF1_4") (pintype "passive"))
    )
    (net (code "71") (name "Net-(U18-RF2)") (class "Default")
      (node (ref "L20") (pin "1") (pinfunction "1_1") (pintype "passive"))
      (node (ref "U18") (pin "17") (pinfunction "RF2_17") (pintype "passive"))
    )
    (net (code "72") (name "Net-(U18-RF3)") (class "Default")
      (node (ref "L22") (pin "1") (pinfunction "1_1") (pintype "passive"))
      (node (ref "U18") (pin "7") (pinfunction "RF3_7") (pintype "passive"))
    )
    (net (code "73") (name "Net-(U18-RF4)") (class "Default")
      (node (ref "L26") (pin "1") (pinfunction "1_1") (pintype "passive"))
      (node (ref "U18") (pin "14") (pinfunction "RF4_14") (pintype "passive"))
    )
  )
)
